# Micro_USB.net
KiCad netlist of a schematic drawn in Altium Designer
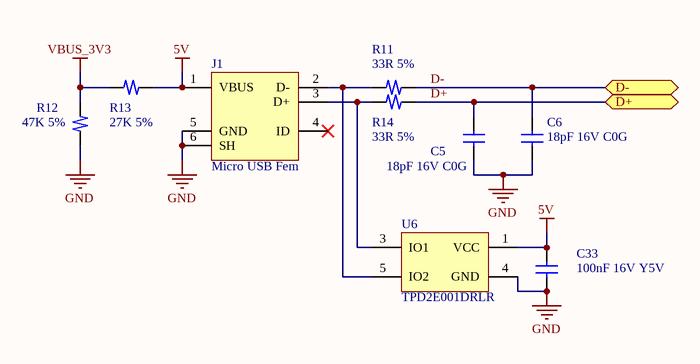
[diagram p0: Micro_USB.SchDoc]

(export (version "E")
  (design (tool "Eeschema 10.0.6"))
  (components
    (comp (ref "C5")
      (value "18pF 16V C0G")
      (footprint "C_0402")
      (description "Ceramic Capacitor SMD 0402")
      (libsource (lib "Oxy_Lib") (part "Ceramic Capacitor"))
    )
    (comp (ref "C6")
      (value "18pF 16V C0G")
      (footprint "C_0402")
      (description "Ceramic Capacitor SMD 0402")
      (libsource (lib "Oxy_Lib") (part "Ceramic Capacitor"))
    )
    (comp (ref "C33")
      (value "100nF 16V Y5V")
      (footprint "C_0402")
      (description "Ceramic Capacitor SMD 0402")
      (libsource (lib "Oxy_Lib") (part "Ceramic Capacitor"))
    )
    (comp (ref "J1")
      (value "Micro USB Fem")
      (footprint "Micro USB")
      (description "Micro-USB 2.0 AB Receptacle, Right Angle, Part Number 47590-0001")
      (libsource (lib "Oxy_Lib") (part "Micro USB Connector"))
    )
    (comp (ref "R11")
      (value "33R 5%")
      (footprint "R_0402")
      (description "Resistor SMD 0402")
      (libsource (lib "Oxy_Lib") (part "Resistor"))
    )
    (comp (ref "R12")
      (value "47K 5%")
      (footprint "R_0402")
      (description "Resistor SMD 0402")
      (libsource (lib "Oxy_Lib") (part "Resistor"))
    )
    (comp (ref "R13")
      (value "27K 5%")
      (footprint "R_0402")
      (description "Resistor SMD 0402")
      (libsource (lib "Oxy_Lib") (part "Resistor"))
    )
    (comp (ref "R14")
      (value "33R 5%")
      (footprint "R_0402")
      (description "Resistor SMD 0402")
      (libsource (lib "Oxy_Lib") (part "Resistor"))
    )
    (comp (ref "U6")
      (value "TPD2E001DRLR")
      (footprint "TPD2E001")
      (description "Low-Capacitance 2-Ch ESD-Protection for High-Speed Data Interfaces, SOT5")
      (libsource (lib "Oxy_Lib") (part "Diode ESD-Protection"))
    )
  )
  (nets
    (net (code "1") (name "/D+") (class "Default")
      (node (ref "C5") (pin "1") (pinfunction "1_1") (pintype "passive"))
      (node (ref "R14") (pin "2") (pinfunction "2_2") (pintype "passive"))
    )
    (net (code "2") (name "/D-") (class "Default")
      (node (ref "C6") (pin "1") (pinfunction "1_1") (pintype "passive"))
      (node (ref "R11") (pin "2") (pinfunction "2_2") (pintype "passive"))
    )
    (net (code "3") (name "5V") (class "Default")
      (node (ref "C33") (pin "1") (pinfunction "1_1") (pintype "passive"))
      (node (ref "J1") (pin "1") (pinfunction "VBUS_1") (pintype "passive"))
      (node (ref "R13") (pin "2") (pinfunction "2_2") (pintype "passive"))
      (node (ref "U6") (pin "1") (pinfunction "VCC_1") (pintype "passive"))
    )
    (net (code "4") (name "GND") (class "Default")
      (node (ref "C33") (pin "2") (pinfunction "2_2") (pintype "passive"))
      (node (ref "C5") (pin "2") (pinfunction "2_2") (pintype "passive"))
      (node (ref "C6") (pin "2") (pinfunction "2_2") (pintype "passive"))
      (node (ref "J1") (pin "5") (pinfunction "GND_5") (pintype "passive"))
      (node (ref "J1") (pin "6") (pinfunction "SH_6") (pintype "passive"))
      (node (ref "R12") (pin "1") (pinfunction "1_1") (pintype "passive"))
      (node (ref "U6") (pin "4") (pinfunction "GND_4") (pintype "passive"))
    )
    (net (code "5") (name "Net-(J1-D+)") (class "Default")
      (node (ref "J1") (pin "3") (pinfunction "D+_3") (pintype "passive"))
      (node (ref "R14") (pin "1") (pinfunction "1_1") (pintype "passive"))
      (node (ref "U6") (pin "3") (pinfunction "IO1_3") (pintype "passive"))
    )
    (net (code "6") (name "Net-(J1-D-)") (class "Default")
      (node (ref "J1") (pin "2") (pinfunction "D-_2") (pintype "passive"))
      (node (ref "R11") (pin "1") (pinfunction "1_1") (pintype "passive"))
      (node (ref "U6") (pin "5") (pinfunction "IO2_5") (pintype "passive"))
    )
    (net (code "7") (name "VBUS_3V3") (class "Default")
      (node (ref "R12") (pin "2") (pinfunction "2_2") (pintype "passive"))
      (node (ref "R13") (pin "1") (pinfunction "1_1") (pintype "passive"))
    )
    (net (code "8") (name "unconnected-(J1-ID-Pad4)") (class "Default")
      (node (ref "J1") (pin "4") (pinfunction "ID_4") (pintype "passive+no_connect"))
    )
  )
)
